# Emat_300v.net
KiCad netlist of a schematic drawn in EAGLE
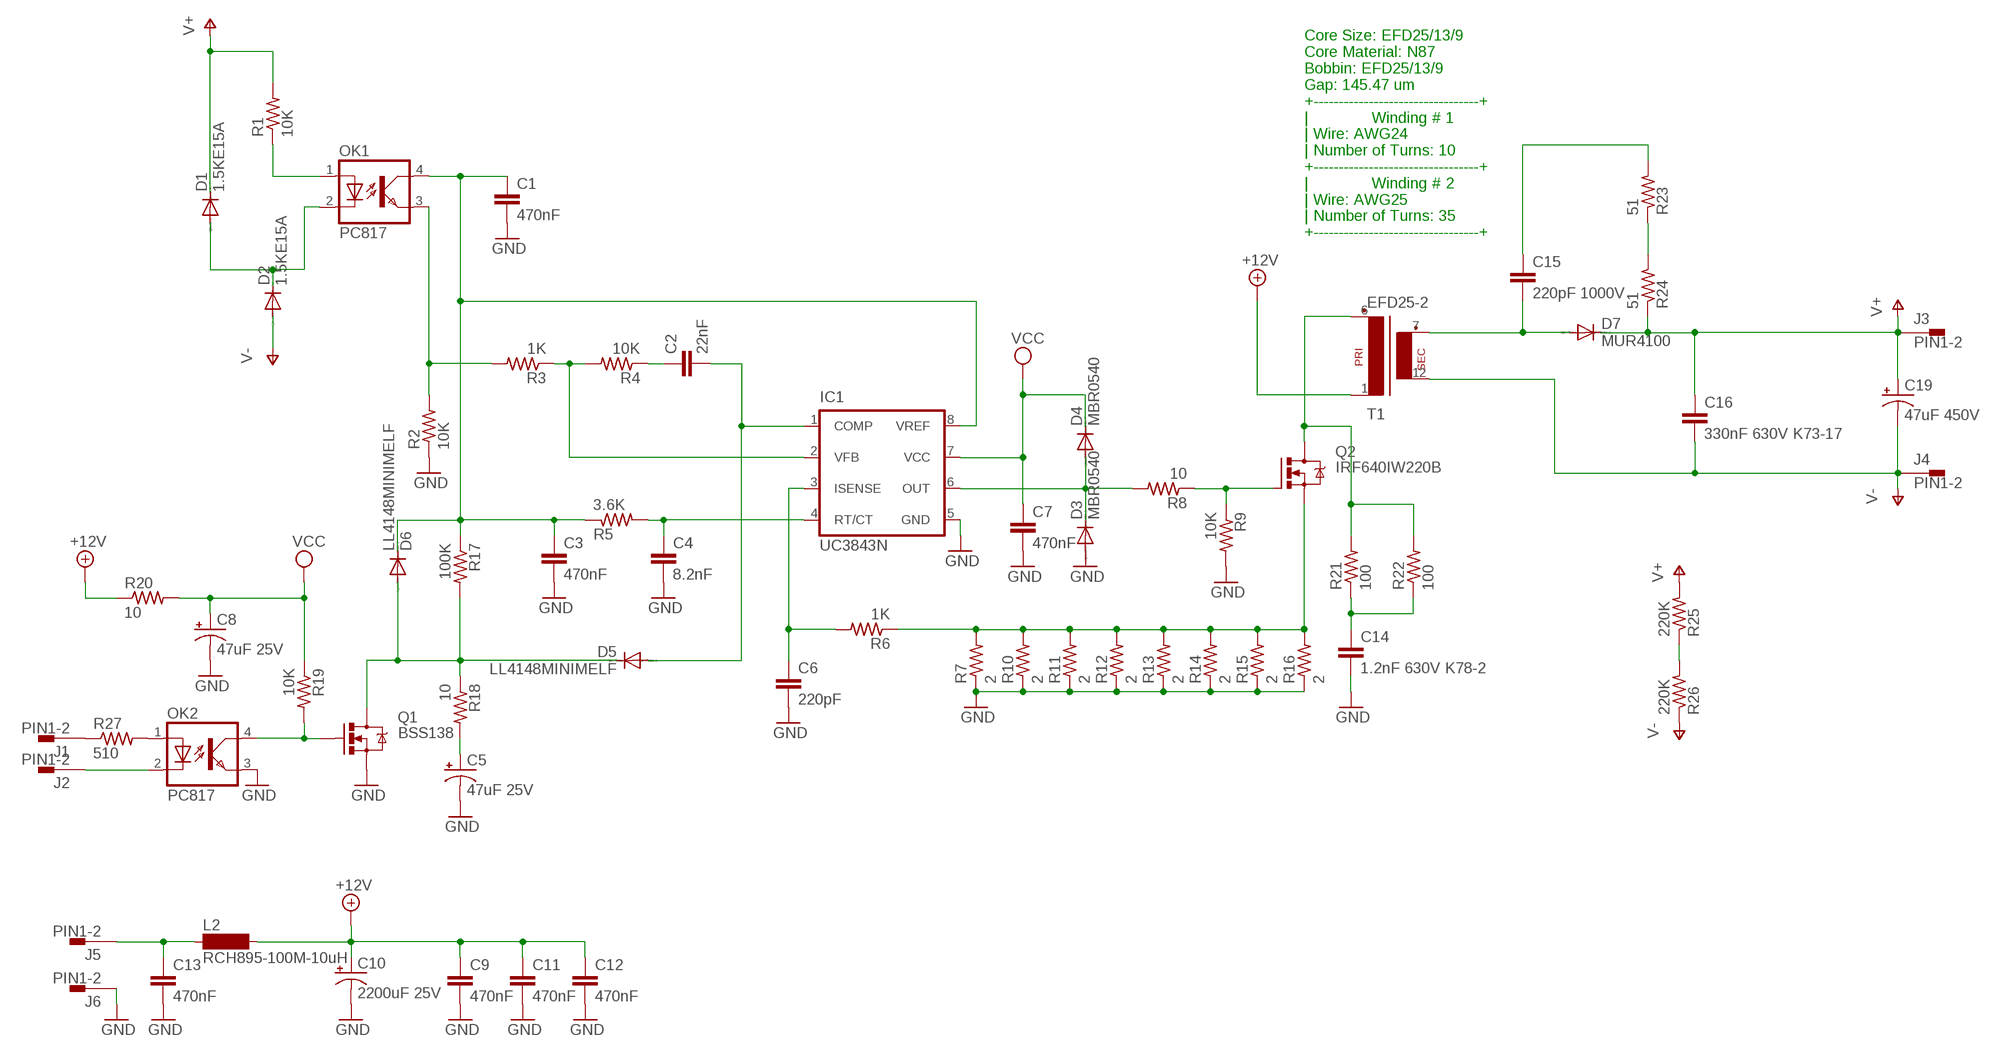
[diagram p0: schematic, sheet 1]

(export (version "E")
  (design (tool "Eeschema 10.0.6"))
  (components
    (comp (ref "C1")
      (value "470nF")
      (footprint "eagle-import:C0805")
      (libsource (lib "eagle-import") (part "C-EUC0805"))
    )
    (comp (ref "C2")
      (value "22nF")
      (footprint "eagle-import:C0805")
      (libsource (lib "eagle-import") (part "C-EUC0805"))
    )
    (comp (ref "C3")
      (value "470nF")
      (footprint "eagle-import:C0805")
      (libsource (lib "eagle-import") (part "C-EUC0805"))
    )
    (comp (ref "C4")
      (value "8.2nF")
      (footprint "eagle-import:C0805")
      (libsource (lib "eagle-import") (part "C-EUC0805"))
    )
    (comp (ref "C5")
      (value "47uF 25V")
      (footprint "eagle-import:E5-8,5")
      (libsource (lib "eagle-import") (part "CPOL-USE5-8.5"))
    )
    (comp (ref "C6")
      (value "220pF")
      (footprint "eagle-import:C0805")
      (libsource (lib "eagle-import") (part "C-EUC0805"))
    )
    (comp (ref "C7")
      (value "470nF")
      (footprint "eagle-import:C0805")
      (libsource (lib "eagle-import") (part "C-EUC0805"))
    )
    (comp (ref "C8")
      (value "47uF 25V")
      (footprint "eagle-import:E5-8,5")
      (libsource (lib "eagle-import") (part "CPOL-USE5-8.5"))
    )
    (comp (ref "C9")
      (value "470nF")
      (footprint "eagle-import:C0805")
      (libsource (lib "eagle-import") (part "C-EUC0805"))
    )
    (comp (ref "C10")
      (value "2200uF 25V")
      (footprint "eagle-import:E7,5-18")
      (libsource (lib "eagle-import") (part "CPOL-USE7.5-18"))
    )
    (comp (ref "C11")
      (value "470nF")
      (footprint "eagle-import:C0805")
      (libsource (lib "eagle-import") (part "C-EUC0805"))
    )
    (comp (ref "C12")
      (value "470nF")
      (footprint "eagle-import:C0805")
      (libsource (lib "eagle-import") (part "C-EUC0805"))
    )
    (comp (ref "C13")
      (value "470nF")
      (footprint "eagle-import:C0805")
      (libsource (lib "eagle-import") (part "C-EUC0805"))
    )
    (comp (ref "C14")
      (value "1.2nF 630V K78-2")
      (footprint "eagle-import:C150-064X183")
      (libsource (lib "eagle-import") (part "C-EU150-064X183"))
    )
    (comp (ref "C15")
      (value "220pF 1000V")
      (footprint "eagle-import:C075-042X103")
      (libsource (lib "eagle-import") (part "C-EU075-042X103"))
    )
    (comp (ref "C16")
      (value "330nF 630V K73-17")
      (footprint "eagle-import:C225-062X268")
      (libsource (lib "eagle-import") (part "C-EU225-062X268"))
    )
    (comp (ref "C19")
      (value "47uF 450V")
      (footprint "eagle-import:E7,5-18")
      (libsource (lib "eagle-import") (part "CPOL-USE7.5-18"))
    )
    (comp (ref "D1")
      (value "1.5KE15A")
      (footprint "eagle-import:DO201-15")
      (libsource (lib "eagle-import") (part "DIODE-DO201-15"))
    )
    (comp (ref "D2")
      (value "1.5KE15A")
      (footprint "eagle-import:DO201-15")
      (libsource (lib "eagle-import") (part "DIODE-DO201-15"))
    )
    (comp (ref "D3")
      (value "MBR0540")
      (footprint "eagle-import:SOD123")
      (libsource (lib "eagle-import") (part "DIODE-SOD123"))
    )
    (comp (ref "D4")
      (value "MBR0540")
      (footprint "eagle-import:SOD123")
      (libsource (lib "eagle-import") (part "DIODE-SOD123"))
    )
    (comp (ref "D5")
      (value "LL4148MINIMELF")
      (footprint "eagle-import:MINIMELF")
      (libsource (lib "eagle-import") (part "LL4148MINIMELF"))
    )
    (comp (ref "D6")
      (value "LL4148MINIMELF")
      (footprint "eagle-import:MINIMELF")
      (libsource (lib "eagle-import") (part "LL4148MINIMELF"))
    )
    (comp (ref "D7")
      (value "MUR4100")
      (footprint "eagle-import:DO201-15")
      (libsource (lib "eagle-import") (part "DIODE-DO201-15"))
    )
    (comp (ref "IC1")
      (value "UC3843N")
      (footprint "eagle-import:DIL08")
      (libsource (lib "eagle-import") (part "UC384N3"))
    )
    (comp (ref "J1")
      (value "PIN1-2")
      (footprint "eagle-import:62221")
      (fields (field (name "MF") "TYCO ELECTRONICS") (field (name "MPN") "62221-1"))
      (libsource (lib "eagle-import") (part "PIN1-2"))
    )
    (comp (ref "J2")
      (value "PIN1-2")
      (footprint "eagle-import:62221")
      (fields (field (name "MF") "TYCO ELECTRONICS") (field (name "MPN") "62221-1"))
      (libsource (lib "eagle-import") (part "PIN1-2"))
    )
    (comp (ref "J3")
      (value "PIN1-2")
      (footprint "eagle-import:62221")
      (fields (field (name "MF") "TYCO ELECTRONICS") (field (name "MPN") "62221-1"))
      (libsource (lib "eagle-import") (part "PIN1-2"))
    )
    (comp (ref "J4")
      (value "PIN1-2")
      (footprint "eagle-import:62221")
      (fields (field (name "MF") "TYCO ELECTRONICS") (field (name "MPN") "62221-1"))
      (libsource (lib "eagle-import") (part "PIN1-2"))
    )
    (comp (ref "J5")
      (value "PIN1-2")
      (footprint "eagle-import:62221")
      (fields (field (name "MF") "TYCO ELECTRONICS") (field (name "MPN") "62221-1"))
      (libsource (lib "eagle-import") (part "PIN1-2"))
    )
    (comp (ref "J6")
      (value "PIN1-2")
      (footprint "eagle-import:62221")
      (fields (field (name "MF") "TYCO ELECTRONICS") (field (name "MPN") "62221-1"))
      (libsource (lib "eagle-import") (part "PIN1-2"))
    )
    (comp (ref "L2")
      (value "RCH895-100M-10uH")
      (footprint "eagle-import:BS11")
      (libsource (lib "eagle-import") (part "RCH-89511"))
    )
    (comp (ref "OK1")
      (value "PC817")
      (footprint "eagle-import:DIL04")
      (fields (field (name "MPN") "PC817X4J000F"))
      (libsource (lib "eagle-import") (part "PC817"))
    )
    (comp (ref "OK2")
      (value "PC817")
      (footprint "eagle-import:DIL04")
      (fields (field (name "MPN") "PC817X4J000F"))
      (libsource (lib "eagle-import") (part "PC817"))
    )
    (comp (ref "Q1")
      (value "BSS138")
      (footprint "eagle-import:SOT23-3")
      (libsource (lib "eagle-import") (part "MOSFET-NCHANNELBSS138"))
    )
    (comp (ref "Q2")
      (value "IRF640IW220B")
      (footprint "eagle-import:IW220B")
      (libsource (lib "eagle-import") (part "IRF640IW220B"))
    )
    (comp (ref "R1")
      (value "10K")
      (footprint "eagle-import:R1206")
      (libsource (lib "eagle-import") (part "R-US_R1206"))
    )
    (comp (ref "R2")
      (value "10K")
      (footprint "eagle-import:R1206")
      (libsource (lib "eagle-import") (part "R-US_R1206"))
    )
    (comp (ref "R3")
      (value "1K")
      (footprint "eagle-import:R1206")
      (libsource (lib "eagle-import") (part "R-US_R1206"))
    )
    (comp (ref "R4")
      (value "10K")
      (footprint "eagle-import:R1206")
      (libsource (lib "eagle-import") (part "R-US_R1206"))
    )
    (comp (ref "R5")
      (value "3.6K")
      (footprint "eagle-import:R1206")
      (libsource (lib "eagle-import") (part "R-US_R1206"))
    )
    (comp (ref "R6")
      (value "1K")
      (footprint "eagle-import:R1206")
      (libsource (lib "eagle-import") (part "R-US_R1206"))
    )
    (comp (ref "R7")
      (value "2")
      (footprint "eagle-import:R1206")
      (libsource (lib "eagle-import") (part "R-US_R1206"))
    )
    (comp (ref "R8")
      (value "10")
      (footprint "eagle-import:R1206")
      (libsource (lib "eagle-import") (part "R-US_R1206"))
    )
    (comp (ref "R9")
      (value "10K")
      (footprint "eagle-import:R1206")
      (libsource (lib "eagle-import") (part "R-US_R1206"))
    )
    (comp (ref "R10")
      (value "2")
      (footprint "eagle-import:R1206")
      (libsource (lib "eagle-import") (part "R-US_R1206"))
    )
    (comp (ref "R11")
      (value "2")
      (footprint "eagle-import:R1206")
      (libsource (lib "eagle-import") (part "R-US_R1206"))
    )
    (comp (ref "R12")
      (value "2")
      (footprint "eagle-import:R1206")
      (libsource (lib "eagle-import") (part "R-US_R1206"))
    )
    (comp (ref "R13")
      (value "2")
      (footprint "eagle-import:R1206")
      (libsource (lib "eagle-import") (part "R-US_R1206"))
    )
    (comp (ref "R14")
      (value "2")
      (footprint "eagle-import:R1206")
      (libsource (lib "eagle-import") (part "R-US_R1206"))
    )
    (comp (ref "R15")
      (value "2")
      (footprint "eagle-import:R1206")
      (libsource (lib "eagle-import") (part "R-US_R1206"))
    )
    (comp (ref "R16")
      (value "2")
      (footprint "eagle-import:R1206")
      (libsource (lib "eagle-import") (part "R-US_R1206"))
    )
    (comp (ref "R17")
      (value "100K")
      (footprint "eagle-import:R1206")
      (libsource (lib "eagle-import") (part "R-US_R1206"))
    )
    (comp (ref "R18")
      (value "10")
      (footprint "eagle-import:R1206")
      (libsource (lib "eagle-import") (part "R-US_R1206"))
    )
    (comp (ref "R19")
      (value "10K")
      (footprint "eagle-import:R1206")
      (libsource (lib "eagle-import") (part "R-US_R1206"))
    )
    (comp (ref "R20")
      (value "10")
      (footprint "eagle-import:R1206")
      (libsource (lib "eagle-import") (part "R-US_R1206"))
    )
    (comp (ref "R21")
      (value "100")
      (footprint "eagle-import:R2512")
      (libsource (lib "eagle-import") (part "R-US_R2512"))
    )
    (comp (ref "R22")
      (value "100")
      (footprint "eagle-import:R2512")
      (libsource (lib "eagle-import") (part "R-US_R2512"))
    )
    (comp (ref "R23")
      (value "51")
      (footprint "eagle-import:R1206")
      (libsource (lib "eagle-import") (part "R-US_R1206"))
    )
    (comp (ref "R24")
      (value "51")
      (footprint "eagle-import:R1206")
      (libsource (lib "eagle-import") (part "R-US_R1206"))
    )
    (comp (ref "R25")
      (value "220K")
      (footprint "eagle-import:R1206")
      (libsource (lib "eagle-import") (part "R-US_R1206"))
    )
    (comp (ref "R26")
      (value "220K")
      (footprint "eagle-import:R1206")
      (libsource (lib "eagle-import") (part "R-US_R1206"))
    )
    (comp (ref "R27")
      (value "510")
      (footprint "eagle-import:R1206")
      (libsource (lib "eagle-import") (part "R-US_R1206"))
    )
    (comp (ref "T1")
      (value "EFD25-2")
      (footprint "eagle-import:EFD25")
      (libsource (lib "eagle-import") (part "EFD25-2"))
    )
  )
  (nets
    (net (code "1") (name "+12V") (class "Default")
      (node (ref "C10") (pin "+") (pinfunction "+_+") (pintype "passive"))
      (node (ref "C11") (pin "1") (pinfunction "1_1") (pintype "passive"))
      (node (ref "C12") (pin "1") (pinfunction "1_1") (pintype "passive"))
      (node (ref "C9") (pin "1") (pinfunction "1_1") (pintype "passive"))
      (node (ref "L2") (pin "2") (pinfunction "2_2") (pintype "passive"))
      (node (ref "R20") (pin "1") (pinfunction "1_1") (pintype "passive"))
      (node (ref "T1") (pin "1") (pinfunction "P1_1") (pintype "passive"))
    )
    (net (code "2") (name "GND") (class "Default")
      (node (ref "C1") (pin "2") (pinfunction "2_2") (pintype "passive"))
      (node (ref "C10") (pin "-") (pinfunction "-_-") (pintype "passive"))
      (node (ref "C11") (pin "2") (pinfunction "2_2") (pintype "passive"))
      (node (ref "C12") (pin "2") (pinfunction "2_2") (pintype "passive"))
      (node (ref "C13") (pin "2") (pinfunction "2_2") (pintype "passive"))
      (node (ref "C14") (pin "2") (pinfunction "2_2") (pintype "passive"))
      (node (ref "C3") (pin "2") (pinfunction "2_2") (pintype "passive"))
      (node (ref "C4") (pin "2") (pinfunction "2_2") (pintype "passive"))
      (node (ref "C5") (pin "-") (pinfunction "-_-") (pintype "passive"))
      (node (ref "C6") (pin "2") (pinfunction "2_2") (pintype "passive"))
      (node (ref "C7") (pin "2") (pinfunction "2_2") (pintype "passive"))
      (node (ref "C8") (pin "-") (pinfunction "-_-") (pintype "passive"))
      (node (ref "C9") (pin "2") (pinfunction "2_2") (pintype "passive"))
      (node (ref "D3") (pin "A") (pinfunction "A_A") (pintype "passive"))
      (node (ref "IC1") (pin "5") (pinfunction "GND_5") (pintype "power_in"))
      (node (ref "J6") (pin "1") (pinfunction "1_1") (pintype "passive"))
      (node (ref "OK2") (pin "3") (pinfunction "EMIT_3") (pintype "passive"))
      (node (ref "Q1") (pin "2") (pinfunction "S_2") (pintype "passive"))
      (node (ref "R10") (pin "1") (pinfunction "1_1") (pintype "passive"))
      (node (ref "R11") (pin "1") (pinfunction "1_1") (pintype "passive"))
      (node (ref "R12") (pin "1") (pinfunction "1_1") (pintype "passive"))
      (node (ref "R13") (pin "1") (pinfunction "1_1") (pintype "passive"))
      (node (ref "R14") (pin "1") (pinfunction "1_1") (pintype "passive"))
      (node (ref "R15") (pin "1") (pinfunction "1_1") (pintype "passive"))
      (node (ref "R16") (pin "1") (pinfunction "1_1") (pintype "passive"))
      (node (ref "R2") (pin "1") (pinfunction "1_1") (pintype "passive"))
      (node (ref "R7") (pin "1") (pinfunction "1_1") (pintype "passive"))
      (node (ref "R9") (pin "2") (pinfunction "2_2") (pintype "passive"))
    )
    (net (code "3") (name "Net-(C2-Pad1)") (class "Default")
      (node (ref "C2") (pin "1") (pinfunction "1_1") (pintype "passive"))
      (node (ref "R4") (pin "1") (pinfunction "1_1") (pintype "passive"))
    )
    (net (code "4") (name "Net-(C5-Pad+)") (class "Default")
      (node (ref "C5") (pin "+") (pinfunction "+_+") (pintype "passive"))
      (node (ref "R18") (pin "2") (pinfunction "2_2") (pintype "passive"))
    )
    (net (code "5") (name "Net-(C13-Pad1)") (class "Default")
      (node (ref "C13") (pin "1") (pinfunction "1_1") (pintype "passive"))
      (node (ref "J5") (pin "1") (pinfunction "1_1") (pintype "passive"))
      (node (ref "L2") (pin "1") (pinfunction "1_1") (pintype "passive"))
    )
    (net (code "6") (name "Net-(C14-Pad1)") (class "Default")
      (node (ref "C14") (pin "1") (pinfunction "1_1") (pintype "passive"))
      (node (ref "R21") (pin "1") (pinfunction "1_1") (pintype "passive"))
      (node (ref "R22") (pin "1") (pinfunction "1_1") (pintype "passive"))
    )
    (net (code "7") (name "Net-(C15-Pad1)") (class "Default")
      (node (ref "C15") (pin "1") (pinfunction "1_1") (pintype "passive"))
      (node (ref "R23") (pin "2") (pinfunction "2_2") (pintype "passive"))
    )
    (net (code "8") (name "Net-(IC1-COMP)") (class "Default")
      (node (ref "C2") (pin "2") (pinfunction "2_2") (pintype "passive"))
      (node (ref "D5") (pin "A") (pinfunction "A_A") (pintype "passive"))
      (node (ref "IC1") (pin "1") (pinfunction "COMP_1") (pintype "passive"))
    )
    (net (code "9") (name "Net-(IC1-ISENSE)") (class "Default")
      (node (ref "C6") (pin "1") (pinfunction "1_1") (pintype "passive"))
      (node (ref "IC1") (pin "3") (pinfunction "ISENSE_3") (pintype "input"))
      (node (ref "R6") (pin "2") (pinfunction "2_2") (pintype "passive"))
    )
    (net (code "10") (name "Net-(IC1-OUT)") (class "Default")
      (node (ref "D3") (pin "C") (pinfunction "C_C") (pintype "passive"))
      (node (ref "D4") (pin "A") (pinfunction "A_A") (pintype "passive"))
      (node (ref "IC1") (pin "6") (pinfunction "OUT_6") (pintype "output"))
      (node (ref "R8") (pin "2") (pinfunction "2_2") (pintype "passive"))
    )
    (net (code "11") (name "Net-(IC1-RT{slash}CT)") (class "Default")
      (node (ref "C4") (pin "1") (pinfunction "1_1") (pintype "passive"))
      (node (ref "IC1") (pin "4") (pinfunction "RT/CT_4") (pintype "passive"))
      (node (ref "R5") (pin "2") (pinfunction "2_2") (pintype "passive"))
    )
    (net (code "12") (name "Net-(IC1-VFB)") (class "Default")
      (node (ref "IC1") (pin "2") (pinfunction "VFB_2") (pintype "input"))
      (node (ref "R3") (pin "1") (pinfunction "1_1") (pintype "passive"))
      (node (ref "R4") (pin "2") (pinfunction "2_2") (pintype "passive"))
    )
    (net (code "13") (name "Net-(IC1-VREF)") (class "Default")
      (node (ref "C1") (pin "1") (pinfunction "1_1") (pintype "passive"))
      (node (ref "C3") (pin "1") (pinfunction "1_1") (pintype "passive"))
      (node (ref "D6") (pin "C") (pinfunction "C_C") (pintype "passive"))
      (node (ref "IC1") (pin "8") (pinfunction "VREF_8") (pintype "passive"))
      (node (ref "OK1") (pin "4") (pinfunction "COL_4") (pintype "passive"))
      (node (ref "R17") (pin "1") (pinfunction "1_1") (pintype "passive"))
      (node (ref "R5") (pin "1") (pinfunction "1_1") (pintype "passive"))
    )
    (net (code "14") (name "Net-(J1-Pad1)") (class "Default")
      (node (ref "J1") (pin "1") (pinfunction "1_1") (pintype "passive"))
      (node (ref "R27") (pin "1") (pinfunction "1_1") (pintype "passive"))
    )
    (net (code "15") (name "Net-(OK1-A)") (class "Default")
      (node (ref "OK1") (pin "1") (pinfunction "A_1") (pintype "passive"))
      (node (ref "R1") (pin "1") (pinfunction "1_1") (pintype "passive"))
    )
    (net (code "16") (name "Net-(OK1-C)") (class "Default")
      (node (ref "D1") (pin "A") (pinfunction "A_A") (pintype "passive"))
      (node (ref "D2") (pin "C") (pinfunction "C_C") (pintype "passive"))
      (node (ref "OK1") (pin "2") (pinfunction "C_2") (pintype "passive"))
    )
    (net (code "17") (name "Net-(OK1-EMIT)") (class "Default")
      (node (ref "OK1") (pin "3") (pinfunction "EMIT_3") (pintype "passive"))
      (node (ref "R2") (pin "2") (pinfunction "2_2") (pintype "passive"))
      (node (ref "R3") (pin "2") (pinfunction "2_2") (pintype "passive"))
    )
    (net (code "18") (name "Net-(OK2-A)") (class "Default")
      (node (ref "OK2") (pin "1") (pinfunction "A_1") (pintype "passive"))
      (node (ref "R27") (pin "2") (pinfunction "2_2") (pintype "passive"))
    )
    (net (code "19") (name "Net-(OK2-C)") (class "Default")
      (node (ref "J2") (pin "1") (pinfunction "1_1") (pintype "passive"))
      (node (ref "OK2") (pin "2") (pinfunction "C_2") (pintype "passive"))
    )
    (net (code "20") (name "Net-(OK2-COL)") (class "Default")
      (node (ref "OK2") (pin "4") (pinfunction "COL_4") (pintype "passive"))
      (node (ref "Q1") (pin "1") (pinfunction "G_1") (pintype "passive"))
      (node (ref "R19") (pin "2") (pinfunction "2_2") (pintype "passive"))
    )
    (net (code "21") (name "Net-(Q1-D)") (class "Default")
      (node (ref "D5") (pin "C") (pinfunction "C_C") (pintype "passive"))
      (node (ref "D6") (pin "A") (pinfunction "A_A") (pintype "passive"))
      (node (ref "Q1") (pin "3") (pinfunction "D_3") (pintype "passive"))
      (node (ref "R17") (pin "2") (pinfunction "2_2") (pintype "passive"))
      (node (ref "R18") (pin "1") (pinfunction "1_1") (pintype "passive"))
    )
    (net (code "22") (name "Net-(Q2-PadG)") (class "Default")
      (node (ref "Q2") (pin "G") (pinfunction "G_G") (pintype "passive"))
      (node (ref "R8") (pin "1") (pinfunction "1_1") (pintype "passive"))
      (node (ref "R9") (pin "1") (pinfunction "1_1") (pintype "passive"))
    )
    (net (code "23") (name "Net-(Q2-PadS)") (class "Default")
      (node (ref "Q2") (pin "S") (pinfunction "S_S") (pintype "passive"))
      (node (ref "R10") (pin "2") (pinfunction "2_2") (pintype "passive"))
      (node (ref "R11") (pin "2") (pinfunction "2_2") (pintype "passive"))
      (node (ref "R12") (pin "2") (pinfunction "2_2") (pintype "passive"))
      (node (ref "R13") (pin "2") (pinfunction "2_2") (pintype "passive"))
      (node (ref "R14") (pin "2") (pinfunction "2_2") (pintype "passive"))
      (node (ref "R15") (pin "2") (pinfunction "2_2") (pintype "passive"))
      (node (ref "R16") (pin "2") (pinfunction "2_2") (pintype "passive"))
      (node (ref "R6") (pin "1") (pinfunction "1_1") (pintype "passive"))
      (node (ref "R7") (pin "2") (pinfunction "2_2") (pintype "passive"))
    )
    (net (code "24") (name "Net-(R23-Pad1)") (class "Default")
      (node (ref "R23") (pin "1") (pinfunction "1_1") (pintype "passive"))
      (node (ref "R24") (pin "2") (pinfunction "2_2") (pintype "passive"))
    )
    (net (code "25") (name "Net-(R25-Pad1)") (class "Default")
      (node (ref "R25") (pin "1") (pinfunction "1_1") (pintype "passive"))
      (node (ref "R26") (pin "2") (pinfunction "2_2") (pintype "passive"))
    )
    (net (code "26") (name "Net-(T1-P2)") (class "Default")
      (node (ref "Q2") (pin "D") (pinfunction "D_D") (pintype "passive"))
      (node (ref "R21") (pin "2") (pinfunction "2_2") (pintype "passive"))
      (node (ref "R22") (pin "2") (pinfunction "2_2") (pintype "passive"))
      (node (ref "T1") (pin "6") (pinfunction "P2_6") (pintype "passive"))
    )
    (net (code "27") (name "Net-(T1-S1)") (class "Default")
      (node (ref "C15") (pin "2") (pinfunction "2_2") (pintype "passive"))
      (node (ref "D7") (pin "A") (pinfunction "A_A") (pintype "passive"))
      (node (ref "T1") (pin "7") (pinfunction "S1_7") (pintype "passive"))
    )
    (net (code "28") (name "V+") (class "Default")
      (node (ref "C16") (pin "1") (pinfunction "1_1") (pintype "passive"))
      (node (ref "C19") (pin "+") (pinfunction "+_+") (pintype "passive"))
      (node (ref "D1") (pin "C") (pinfunction "C_C") (pintype "passive"))
      (node (ref "D7") (pin "C") (pinfunction "C_C") (pintype "passive"))
      (node (ref "J3") (pin "1") (pinfunction "1_1") (pintype "passive"))
      (node (ref "R1") (pin "2") (pinfunction "2_2") (pintype "passive"))
      (node (ref "R24") (pin "1") (pinfunction "1_1") (pintype "passive"))
      (node (ref "R25") (pin "2") (pinfunction "2_2") (pintype "passive"))
    )
    (net (code "29") (name "V-") (class "Default")
      (node (ref "C16") (pin "2") (pinfunction "2_2") (pintype "passive"))
      (node (ref "C19") (pin "-") (pinfunction "-_-") (pintype "passive"))
      (node (ref "D2") (pin "A") (pinfunction "A_A") (pintype "passive"))
      (node (ref "J4") (pin "1") (pinfunction "1_1") (pintype "passive"))
      (node (ref "R26") (pin "1") (pinfunction "1_1") (pintype "passive"))
      (node (ref "T1") (pin "12") (pinfunction "S2_12") (pintype "passive"))
    )
    (net (code "30") (name "VCC") (class "Default")
      (node (ref "C7") (pin "1") (pinfunction "1_1") (pintype "passive"))
      (node (ref "C8") (pin "+") (pinfunction "+_+") (pintype "passive"))
      (node (ref "D4") (pin "C") (pinfunction "C_C") (pintype "passive"))
      (node (ref "IC1") (pin "7") (pinfunction "VCC_7") (pintype "power_in"))
      (node (ref "R19") (pin "1") (pinfunction "1_1") (pintype "passive"))
      (node (ref "R20") (pin "2") (pinfunction "2_2") (pintype "passive"))
    )
  )
)
